# gp2y1010.net
KiCad netlist of a schematic drawn in Altium Designer
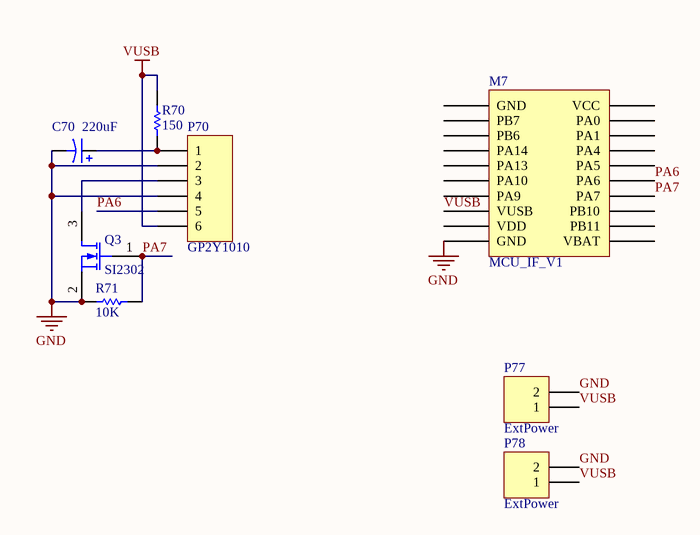
[diagram p0: gp2y1010.SchDoc]

(export (version "E")
  (design (tool "Eeschema 10.0.6"))
  (components
    (comp (ref "C70")
      (value "220uF")
      (footprint "Capacitor_2.4mm_6mm")
      (description "Polarized Capacitor (Radial)")
      (fields (field (name "Comment") "Cap Pol1") (field (name "PUBLISHER") "Altium Limited"))
      (libsource (lib "Miscellaneous Devices") (part "Cap Pol1"))
    )
    (comp (ref "M7")
      (value "MCU_IF_V1")
      (footprint "MCU_IF_V2")
      (libsource (lib "MCU_IF") (part "MCU_IF_V1"))
    )
    (comp (ref "P70")
      (value "GP2Y1010")
      (footprint "GP2Y1010AU0F")
      (description "Header, 6-Pin")
      (fields (field (name "PUBLISHER") "Altium Limited"))
      (libsource (lib "Miscellaneous Connectors") (part "Header 6"))
    )
    (comp (ref "P77")
      (value "ExtPower")
      (footprint "HDR1X2H")
      (description "Header, 2-Pin, Right Angle")
      (fields (field (name "PUBLISHER") "Altium Limited"))
      (libsource (lib "Miscellaneous Connectors") (part "Header 2H"))
    )
    (comp (ref "P78")
      (value "ExtPower")
      (footprint "HDR1X2H")
      (description "Header, 2-Pin, Right Angle")
      (fields (field (name "PUBLISHER") "Altium Limited"))
      (libsource (lib "Miscellaneous Connectors") (part "Header 2H"))
    )
    (comp (ref "Q3")
      (value "SI2302")
      (footprint "SOT23B")
      (description "N-Channel MOSFET")
      (fields (field (name "PUBLISHER") "Altium Limited"))
      (libsource (lib "Schlib1") (part "SI2302"))
    )
    (comp (ref "R70")
      (value "150")
      (footprint "R-1608[0603]")
      (description "Semiconductor Resistor")
      (fields (field (name "Comment") "Res Semi") (field (name "PUBLISHER") "Altium Limited"))
      (libsource (lib "Miscellaneous Devices") (part "Res Semi"))
    )
    (comp (ref "R71")
      (value "10K")
      (footprint "R-1608[0603]")
      (description "Semiconductor Resistor")
      (fields (field (name "Comment") "Res Semi") (field (name "PUBLISHER") "Altium Limited"))
      (libsource (lib "Miscellaneous Devices") (part "Res Semi"))
    )
  )
  (nets
    (net (code "1") (name "/PA6") (class "Default")
      (node (ref "M7") (pin "15") (pinfunction "PA6_15") (pintype "passive"))
      (node (ref "P70") (pin "5") (pinfunction "5_5") (pintype "passive"))
    )
    (net (code "2") (name "/PA7") (class "Default")
      (node (ref "M7") (pin "14") (pinfunction "PA7_14") (pintype "passive"))
      (node (ref "Q3") (pin "1") (pinfunction "G_1") (pintype "passive"))
      (node (ref "R71") (pin "1") (pinfunction "1_1") (pintype "passive"))
    )
    (net (code "3") (name "GND") (class "Default")
      (node (ref "C70") (pin "2") (pinfunction "2_2") (pintype "passive"))
      (node (ref "M7") (pin "10") (pinfunction "GND_10") (pintype "passive"))
      (node (ref "P70") (pin "2") (pinfunction "2_2") (pintype "passive"))
      (node (ref "P70") (pin "4") (pinfunction "4_4") (pintype "passive"))
      (node (ref "P77") (pin "2") (pinfunction "2_2") (pintype "passive"))
      (node (ref "P78") (pin "2") (pinfunction "2_2") (pintype "passive"))
      (node (ref "Q3") (pin "2") (pinfunction "S_2") (pintype "passive"))
      (node (ref "R71") (pin "2") (pinfunction "2_2") (pintype "passive"))
    )
    (net (code "4") (name "Net-(C70-Pad1)") (class "Default")
      (node (ref "C70") (pin "1") (pinfunction "1_1") (pintype "passive"))
      (node (ref "P70") (pin "1") (pinfunction "1_1") (pintype "passive"))
      (node (ref "R70") (pin "1") (pinfunction "1_1") (pintype "passive"))
    )
    (net (code "5") (name "Net-(Q3-D)") (class "Default")
      (node (ref "P70") (pin "3") (pinfunction "3_3") (pintype "passive"))
      (node (ref "Q3") (pin "3") (pinfunction "D_3") (pintype "passive"))
    )
    (net (code "6") (name "VUSB") (class "Default")
      (node (ref "M7") (pin "8") (pinfunction "VUSB_8") (pintype "passive"))
      (node (ref "P70") (pin "6") (pinfunction "6_6") (pintype "passive"))
      (node (ref "P77") (pin "1") (pinfunction "1_1") (pintype "passive"))
      (node (ref "P78") (pin "1") (pinfunction "1_1") (pintype "passive"))
      (node (ref "R70") (pin "2") (pinfunction "2_2") (pintype "passive"))
    )
    (net (code "7") (name "unconnected-(M7-GND-Pad1)") (class "Default")
      (node (ref "M7") (pin "1") (pinfunction "GND_1") (pintype "passive"))
    )
    (net (code "8") (name "unconnected-(M7-PA0-Pad19)") (class "Default")
      (node (ref "M7") (pin "19") (pinfunction "PA0_19") (pintype "passive"))
    )
    (net (code "9") (name "unconnected-(M7-PA1-Pad18)") (class "Default")
      (node (ref "M7") (pin "18") (pinfunction "PA1_18") (pintype "passive"))
    )
    (net (code "10") (name "unconnected-(M7-PA4-Pad17)") (class "Default")
      (node (ref "M7") (pin "17") (pinfunction "PA4_17") (pintype "passive"))
    )
    (net (code "11") (name "unconnected-(M7-PA5-Pad16)") (class "Default")
      (node (ref "M7") (pin "16") (pinfunction "PA5_16") (pintype "passive"))
    )
    (net (code "12") (name "unconnected-(M7-PA9-Pad7)") (class "Default")
      (node (ref "M7") (pin "7") (pinfunction "PA9_7") (pintype "passive"))
    )
    (net (code "13") (name "unconnected-(M7-PA10-Pad6)") (class "Default")
      (node (ref "M7") (pin "6") (pinfunction "PA10_6") (pintype "passive"))
    )
    (net (code "14") (name "unconnected-(M7-PA13-Pad5)") (class "Default")
      (node (ref "M7") (pin "5") (pinfunction "PA13_5") (pintype "passive"))
    )
    (net (code "15") (name "unconnected-(M7-PA14-Pad4)") (class "Default")
      (node (ref "M7") (pin "4") (pinfunction "PA14_4") (pintype "passive"))
    )
    (net (code "16") (name "unconnected-(M7-PB6-Pad3)") (class "Default")
      (node (ref "M7") (pin "3") (pinfunction "PB6_3") (pintype "passive"))
    )
    (net (code "17") (name "unconnected-(M7-PB7-Pad2)") (class "Default")
      (node (ref "M7") (pin "2") (pinfunction "PB7_2") (pintype "passive"))
    )
    (net (code "18") (name "unconnected-(M7-PB10-Pad13)") (class "Default")
      (node (ref "M7") (pin "13") (pinfunction "PB10_13") (pintype "passive"))
    )
    (net (code "19") (name "unconnected-(M7-PB11-Pad12)") (class "Default")
      (node (ref "M7") (pin "12") (pinfunction "PB11_12") (pintype "passive"))
    )
    (net (code "20") (name "unconnected-(M7-VBAT-Pad11)") (class "Default")
      (node (ref "M7") (pin "11") (pinfunction "VBAT_11") (pintype "passive"))
    )
    (net (code "21") (name "unconnected-(M7-VCC-Pad20)") (class "Default")
      (node (ref "M7") (pin "20") (pinfunction "VCC_20") (pintype "passive"))
    )
    (net (code "22") (name "unconnected-(M7-VDD-Pad9)") (class "Default")
      (node (ref "M7") (pin "9") (pinfunction "VDD_9") (pintype "passive"))
    )
  )
)
